# SparkFun_QwiicBus-Midpoint.net
KiCad netlist of a schematic drawn in EAGLE
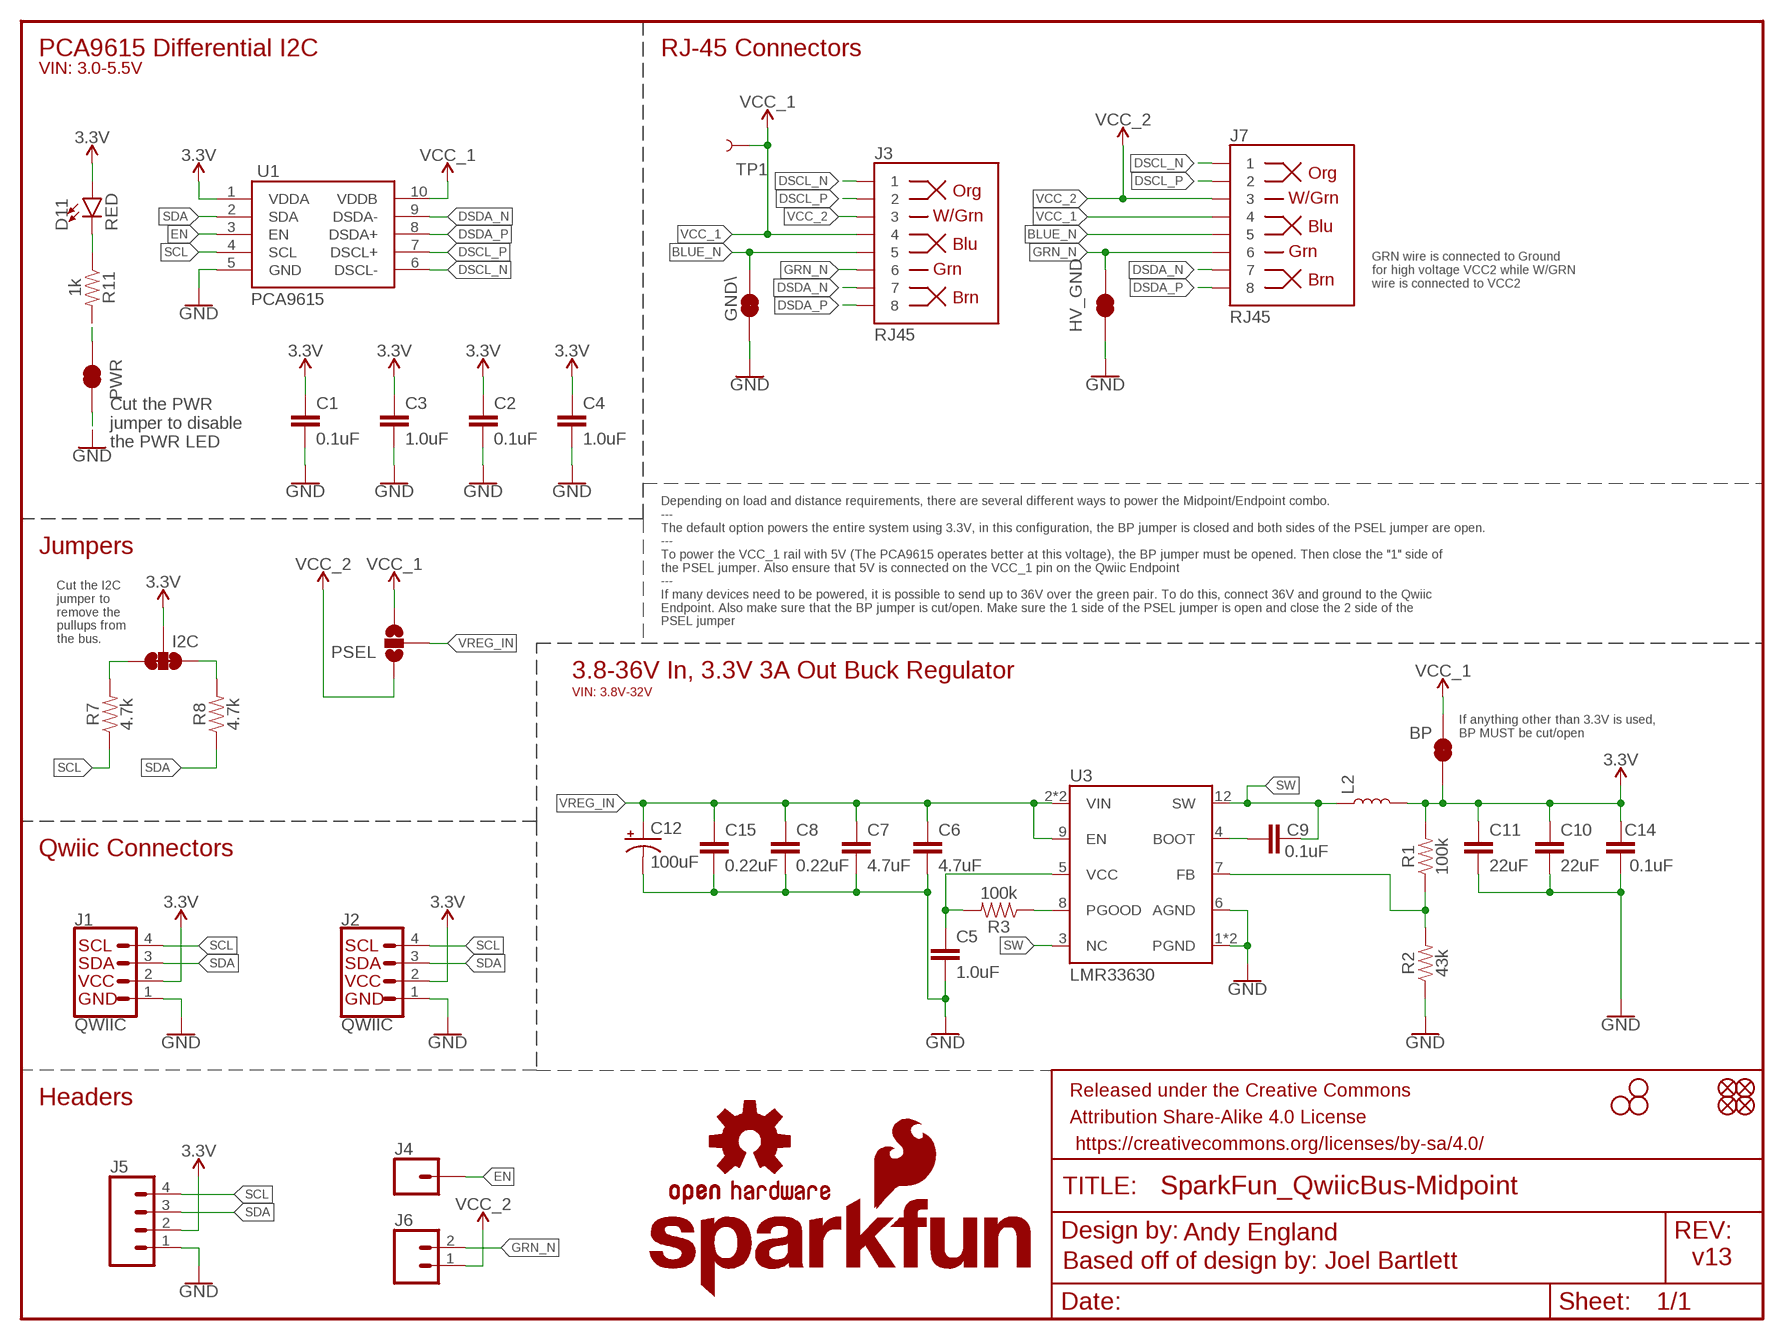
[diagram p0: schematic, sheet 1]

(export (version "E")
  (design (tool "Eeschema 10.0.6"))
  (components
    (comp (ref "BP")
      (value "JUMPER-SMT_2_NC_TRACE_SILK")
      (footprint "eagle-import:SMT-JUMPER_2_NC_TRACE_SILK")
      (libsource (lib "eagle-import") (part "JUMPER-SMT_2_NC_TRACE_SILK"))
    )
    (comp (ref "C1")
      (value "0.1uF")
      (footprint "eagle-import:0603")
      (libsource (lib "eagle-import") (part "0.1UF-0603-25V-(+80/-20%)"))
    )
    (comp (ref "C2")
      (value "0.1uF")
      (footprint "eagle-import:0603")
      (libsource (lib "eagle-import") (part "0.1UF-0603-25V-(+80/-20%)"))
    )
    (comp (ref "C3")
      (value "1.0uF")
      (footprint "eagle-import:0603")
      (libsource (lib "eagle-import") (part "1.0UF-0603-16V-10%"))
    )
    (comp (ref "C4")
      (value "1.0uF")
      (footprint "eagle-import:0603")
      (libsource (lib "eagle-import") (part "1.0UF-0603-16V-10%"))
    )
    (comp (ref "C5")
      (value "1.0uF")
      (footprint "eagle-import:0603")
      (libsource (lib "eagle-import") (part "1.0UF-0603-16V-10%"))
    )
    (comp (ref "C6")
      (value "4.7uF")
      (footprint "eagle-import:0805")
      (libsource (lib "eagle-import") (part "4.7UF-0805-50V-(10%)"))
    )
    (comp (ref "C7")
      (value "4.7uF")
      (footprint "eagle-import:0805")
      (libsource (lib "eagle-import") (part "4.7UF-0805-50V-(10%)"))
    )
    (comp (ref "C8")
      (value "0.22uF")
      (footprint "eagle-import:0603")
      (libsource (lib "eagle-import") (part "0.22UF-0603-50V-10%"))
    )
    (comp (ref "C9")
      (value "0.1uF")
      (footprint "eagle-import:0603")
      (libsource (lib "eagle-import") (part "0.1UF-0603-100V-10%"))
    )
    (comp (ref "C10")
      (value "22uF")
      (footprint "eagle-import:1210")
      (libsource (lib "eagle-import") (part "22UF-1210-16V-20%"))
    )
    (comp (ref "C11")
      (value "22uF")
      (footprint "eagle-import:1210")
      (libsource (lib "eagle-import") (part "22UF-1210-16V-20%"))
    )
    (comp (ref "C12")
      (value "100uF")
      (footprint "eagle-import:8X10.5")
      (libsource (lib "eagle-import") (part "100UF-POLAR-8X10.5-50V"))
    )
    (comp (ref "C14")
      (value "0.1uF")
      (footprint "eagle-import:0603")
      (libsource (lib "eagle-import") (part "0.1UF-0603-100V-10%"))
    )
    (comp (ref "C15")
      (value "0.22uF")
      (footprint "eagle-import:0603")
      (libsource (lib "eagle-import") (part "0.22UF-0603-50V-10%"))
    )
    (comp (ref "D11")
      (value "RED")
      (footprint "eagle-import:LED-0603")
      (libsource (lib "eagle-import") (part "LED-RED0603"))
    )
    (comp (ref "FD1")
      (value "FIDUCIALUFIDUCIAL")
      (footprint "eagle-import:FIDUCIAL-MICRO")
      (libsource (lib "eagle-import") (part "FIDUCIALUFIDUCIAL"))
    )
    (comp (ref "FD2")
      (value "FIDUCIALUFIDUCIAL")
      (footprint "eagle-import:FIDUCIAL-MICRO")
      (libsource (lib "eagle-import") (part "FIDUCIALUFIDUCIAL"))
    )
    (comp (ref "FD3")
      (value "FIDUCIALUFIDUCIAL")
      (footprint "eagle-import:FIDUCIAL-MICRO")
      (libsource (lib "eagle-import") (part "FIDUCIALUFIDUCIAL"))
    )
    (comp (ref "FD4")
      (value "FIDUCIALUFIDUCIAL")
      (footprint "eagle-import:FIDUCIAL-MICRO")
      (libsource (lib "eagle-import") (part "FIDUCIALUFIDUCIAL"))
    )
    (comp (ref "FRAME1")
      (value "FRAME-LETTER")
      (footprint "eagle-import:CREATIVE_COMMONS")
      (libsource (lib "eagle-import") (part "FRAME-LETTER"))
    )
    (comp (ref "GND\\")
      (value "JUMPER-SMT_2_NC_TRACE_SILK")
      (footprint "eagle-import:SMT-JUMPER_2_NC_TRACE_SILK")
      (libsource (lib "eagle-import") (part "JUMPER-SMT_2_NC_TRACE_SILK"))
    )
    (comp (ref "H2")
      (value "STAND-OFF")
      (footprint "eagle-import:STAND-OFF")
      (libsource (lib "eagle-import") (part "STAND-OFF"))
    )
    (comp (ref "H3")
      (value "STAND-OFF")
      (footprint "eagle-import:STAND-OFF")
      (libsource (lib "eagle-import") (part "STAND-OFF"))
    )
    (comp (ref "H4")
      (value "STAND-OFF")
      (footprint "eagle-import:STAND-OFF")
      (libsource (lib "eagle-import") (part "STAND-OFF"))
    )
    (comp (ref "HV_GND")
      (value "JUMPER-SMT_2_NC_TRACE_SILK")
      (footprint "eagle-import:SMT-JUMPER_2_NC_TRACE_SILK")
      (libsource (lib "eagle-import") (part "JUMPER-SMT_2_NC_TRACE_SILK"))
    )
    (comp (ref "I2C")
      (value "JUMPER-SMT_3_2-NC_TRACE_SILK")
      (footprint "eagle-import:SMT-JUMPER_3_2-NC_TRACE_SILK")
      (libsource (lib "eagle-import") (part "JUMPER-SMT_3_2-NC_TRACE_SILK"))
    )
    (comp (ref "J1")
      (value "QWIIC")
      (footprint "eagle-import:JST04_1MM_RA")
      (libsource (lib "eagle-import") (part "QWIIC_CONNECTORJS-1MM"))
    )
    (comp (ref "J2")
      (value "QWIIC")
      (footprint "eagle-import:JST04_1MM_RA")
      (libsource (lib "eagle-import") (part "QWIIC_CONNECTORJS-1MM"))
    )
    (comp (ref "J3")
      (value "RJ45")
      (footprint "eagle-import:RJ45-8")
      (libsource (lib "eagle-import") (part "RJ45-8"))
    )
    (comp (ref "J4")
      (value "CONN_01PTH_NO_SILK_YES_STOP")
      (footprint "eagle-import:1X01_NO_SILK")
      (libsource (lib "eagle-import") (part "CONN_01PTH_NO_SILK_YES_STOP"))
    )
    (comp (ref "J5")
      (value "CONN_041X04_NO_SILK")
      (footprint "eagle-import:1X04_NO_SILK")
      (libsource (lib "eagle-import") (part "CONN_041X04_NO_SILK"))
    )
    (comp (ref "J6")
      (value "CONN_021X02_NO_SILK")
      (footprint "eagle-import:1X02_NO_SILK")
      (libsource (lib "eagle-import") (part "CONN_021X02_NO_SILK"))
    )
    (comp (ref "J7")
      (value "RJ45")
      (footprint "eagle-import:RJ45-8")
      (libsource (lib "eagle-import") (part "RJ45-8"))
    )
    (comp (ref "L2")
      (value "2.2uH")
      (footprint "eagle-import:INDUCTOR_5X5MM")
      (libsource (lib "eagle-import") (part "2.2μH_SHIELDED_INDUCTOR_5X5"))
    )
    (comp (ref "LOGO1")
      (value "OSHW-LOGOM")
      (footprint "eagle-import:OSHW-LOGO-M")
      (libsource (lib "eagle-import") (part "OSHW-LOGOM"))
    )
    (comp (ref "LOGO3")
      (value "SFE_LOGO_FLAME.2_INCH")
      (footprint "eagle-import:SFE_LOGO_FLAME_.2")
      (libsource (lib "eagle-import") (part "SFE_LOGO_FLAME.2_INCH"))
    )
    (comp (ref "LOGO4")
      (value "SFE_LOGO_NAME_FLAME.1_INCH")
      (footprint "eagle-import:SFE_LOGO_NAME_FLAME_.1")
      (libsource (lib "eagle-import") (part "SFE_LOGO_NAME_FLAME.1_INCH"))
    )
    (comp (ref "PSEL")
      (value "JUMPER-SMT_3_NO_SILK")
      (footprint "eagle-import:SMT-JUMPER_3_NO_SILK")
      (libsource (lib "eagle-import") (part "JUMPER-SMT_3_NO_SILK"))
    )
    (comp (ref "PWR")
      (value "JUMPER-SMT_2_NC_TRACE_SILK")
      (footprint "eagle-import:SMT-JUMPER_2_NC_TRACE_SILK")
      (libsource (lib "eagle-import") (part "JUMPER-SMT_2_NC_TRACE_SILK"))
    )
    (comp (ref "R1")
      (value "100k")
      (footprint "eagle-import:0603")
      (libsource (lib "eagle-import") (part "100KOHM-0603-1/10W-1%"))
    )
    (comp (ref "R2")
      (value "43k")
      (footprint "eagle-import:0603")
      (libsource (lib "eagle-import") (part "43KOHM-0603-1/10W-1%"))
    )
    (comp (ref "R3")
      (value "100k")
      (footprint "eagle-import:0603")
      (libsource (lib "eagle-import") (part "100KOHM-0603-1/10W-1%"))
    )
    (comp (ref "R7")
      (value "4.7k")
      (footprint "eagle-import:0603")
      (libsource (lib "eagle-import") (part "4.7KOHM-0603-1/10W-1%"))
    )
    (comp (ref "R8")
      (value "4.7k")
      (footprint "eagle-import:0603")
      (libsource (lib "eagle-import") (part "4.7KOHM-0603-1/10W-1%"))
    )
    (comp (ref "R11")
      (value "1k")
      (footprint "eagle-import:0603")
      (libsource (lib "eagle-import") (part "1KOHM-0603-1/10W-1%"))
    )
    (comp (ref "TP1")
      (value "TEST-POINT3")
      (footprint "eagle-import:PAD.03X.03")
      (libsource (lib "eagle-import") (part "TEST-POINT3"))
    )
    (comp (ref "U1")
      (value "PCA9615")
      (footprint "eagle-import:TSSOP10")
      (libsource (lib "eagle-import") (part "PCA9615"))
    )
    (comp (ref "U3")
      (value "LMR33630")
      (footprint "eagle-import:VQFN-HR-12")
      (libsource (lib "eagle-import") (part "LMR33630"))
    )
  )
  (nets
    (net (code "1") (name "3.3V") (class "Default")
      (node (ref "BP") (pin "1") (pinfunction "1_1") (pintype "passive"))
      (node (ref "C1") (pin "1") (pinfunction "1_1") (pintype "passive"))
      (node (ref "C10") (pin "1") (pinfunction "1_1") (pintype "passive"))
      (node (ref "C11") (pin "1") (pinfunction "1_1") (pintype "passive"))
      (node (ref "C14") (pin "1") (pinfunction "1_1") (pintype "passive"))
      (node (ref "C2") (pin "1") (pinfunction "1_1") (pintype "passive"))
      (node (ref "C3") (pin "1") (pinfunction "1_1") (pintype "passive"))
      (node (ref "C4") (pin "1") (pinfunction "1_1") (pintype "passive"))
      (node (ref "D11") (pin "A") (pinfunction "A_A") (pintype "passive"))
      (node (ref "I2C") (pin "2") (pinfunction "2_2") (pintype "passive"))
      (node (ref "J1") (pin "2") (pinfunction "2_2") (pintype "power_in"))
      (node (ref "J2") (pin "2") (pinfunction "2_2") (pintype "power_in"))
      (node (ref "J5") (pin "2") (pinfunction "2_2") (pintype "passive"))
      (node (ref "L2") (pin "P$2") (pinfunction "2_P$2") (pintype "passive"))
      (node (ref "R1") (pin "2") (pinfunction "2_2") (pintype "passive"))
      (node (ref "U1") (pin "1") (pinfunction "VDDA_1") (pintype "bidirectional"))
    )
    (net (code "2") (name "BLUE_N") (class "Default")
      (node (ref "GND\\") (pin "2") (pinfunction "2_2") (pintype "passive"))
      (node (ref "J3") (pin "5") (pinfunction "5_5") (pintype "bidirectional"))
      (node (ref "J7") (pin "5") (pinfunction "5_5") (pintype "bidirectional"))
    )
    (net (code "3") (name "DSCL_N") (class "Default")
      (node (ref "J3") (pin "1") (pinfunction "1_1") (pintype "bidirectional"))
      (node (ref "J7") (pin "1") (pinfunction "1_1") (pintype "bidirectional"))
      (node (ref "U1") (pin "6") (pinfunction "DSCL-_6") (pintype "bidirectional"))
    )
    (net (code "4") (name "DSCL_P") (class "Default")
      (node (ref "J3") (pin "2") (pinfunction "2_2") (pintype "bidirectional"))
      (node (ref "J7") (pin "2") (pinfunction "2_2") (pintype "bidirectional"))
      (node (ref "U1") (pin "7") (pinfunction "DSCL+_7") (pintype "bidirectional"))
    )
    (net (code "5") (name "DSDA_N") (class "Default")
      (node (ref "J3") (pin "7") (pinfunction "7_7") (pintype "bidirectional"))
      (node (ref "J7") (pin "7") (pinfunction "7_7") (pintype "bidirectional"))
      (node (ref "U1") (pin "9") (pinfunction "DSDA-_9") (pintype "bidirectional"))
    )
    (net (code "6") (name "DSDA_P") (class "Default")
      (node (ref "J3") (pin "8") (pinfunction "8_8") (pintype "bidirectional"))
      (node (ref "J7") (pin "8") (pinfunction "8_8") (pintype "bidirectional"))
      (node (ref "U1") (pin "8") (pinfunction "DSDA+_8") (pintype "bidirectional"))
    )
    (net (code "7") (name "EN") (class "Default")
      (node (ref "J4") (pin "1") (pinfunction "1_1") (pintype "passive"))
      (node (ref "U1") (pin "3") (pinfunction "EN_3") (pintype "bidirectional"))
    )
    (net (code "8") (name "GND") (class "Default")
      (node (ref "C1") (pin "2") (pinfunction "2_2") (pintype "passive"))
      (node (ref "C10") (pin "2") (pinfunction "2_2") (pintype "passive"))
      (node (ref "C11") (pin "2") (pinfunction "2_2") (pintype "passive"))
      (node (ref "C12") (pin "-") (pinfunction "-_-") (pintype "passive"))
      (node (ref "C14") (pin "2") (pinfunction "2_2") (pintype "passive"))
      (node (ref "C15") (pin "2") (pinfunction "2_2") (pintype "passive"))
      (node (ref "C2") (pin "2") (pinfunction "2_2") (pintype "passive"))
      (node (ref "C3") (pin "2") (pinfunction "2_2") (pintype "passive"))
      (node (ref "C4") (pin "2") (pinfunction "2_2") (pintype "passive"))
      (node (ref "C5") (pin "2") (pinfunction "2_2") (pintype "passive"))
      (node (ref "C6") (pin "2") (pinfunction "2_2") (pintype "passive"))
      (node (ref "C7") (pin "2") (pinfunction "2_2") (pintype "passive"))
      (node (ref "C8") (pin "2") (pinfunction "2_2") (pintype "passive"))
      (node (ref "GND\\") (pin "1") (pinfunction "1_1") (pintype "passive"))
      (node (ref "HV_GND") (pin "1") (pinfunction "1_1") (pintype "passive"))
      (node (ref "J1") (pin "1") (pinfunction "1_1") (pintype "power_in"))
      (node (ref "J2") (pin "1") (pinfunction "1_1") (pintype "power_in"))
      (node (ref "J5") (pin "1") (pinfunction "1_1") (pintype "passive"))
      (node (ref "PWR") (pin "1") (pinfunction "1_1") (pintype "passive"))
      (node (ref "R2") (pin "1") (pinfunction "1_1") (pintype "passive"))
      (node (ref "U1") (pin "5") (pinfunction "GND_5") (pintype "bidirectional"))
      (node (ref "U3") (pin "1") (pinfunction "PGND_1") (pintype "bidirectional"))
      (node (ref "U3") (pin "11") (pinfunction "PGND_11") (pintype "bidirectional"))
      (node (ref "U3") (pin "6") (pinfunction "AGND_6") (pintype "bidirectional"))
    )
    (net (code "9") (name "GRN_N") (class "Default")
      (node (ref "HV_GND") (pin "2") (pinfunction "2_2") (pintype "passive"))
      (node (ref "J3") (pin "6") (pinfunction "6_6") (pintype "bidirectional"))
      (node (ref "J6") (pin "2") (pinfunction "2_2") (pintype "passive"))
      (node (ref "J7") (pin "6") (pinfunction "6_6") (pintype "bidirectional"))
    )
    (net (code "10") (name "Net-(D11-PadC)") (class "Default")
      (node (ref "D11") (pin "C") (pinfunction "C_C") (pintype "passive"))
      (node (ref "R11") (pin "1") (pinfunction "1_1") (pintype "passive"))
    )
    (net (code "11") (name "Net-(I2C-Pad1)") (class "Default")
      (node (ref "I2C") (pin "1") (pinfunction "1_1") (pintype "passive"))
      (node (ref "R8") (pin "2") (pinfunction "2_2") (pintype "passive"))
    )
    (net (code "12") (name "Net-(I2C-Pad3)") (class "Default")
      (node (ref "I2C") (pin "3") (pinfunction "3_3") (pintype "passive"))
      (node (ref "R7") (pin "2") (pinfunction "2_2") (pintype "passive"))
    )
    (net (code "13") (name "Net-(PWR-Pad2)") (class "Default")
      (node (ref "PWR") (pin "2") (pinfunction "2_2") (pintype "passive"))
      (node (ref "R11") (pin "2") (pinfunction "2_2") (pintype "passive"))
    )
    (net (code "14") (name "Net-(U3-BOOT)") (class "Default")
      (node (ref "C9") (pin "1") (pinfunction "1_1") (pintype "passive"))
      (node (ref "U3") (pin "4") (pinfunction "BOOT_4") (pintype "bidirectional"))
    )
    (net (code "15") (name "Net-(U3-FB)") (class "Default")
      (node (ref "R1") (pin "1") (pinfunction "1_1") (pintype "passive"))
      (node (ref "R2") (pin "2") (pinfunction "2_2") (pintype "passive"))
      (node (ref "U3") (pin "7") (pinfunction "FB_7") (pintype "bidirectional"))
    )
    (net (code "16") (name "Net-(U3-PGOOD)") (class "Default")
      (node (ref "R3") (pin "1") (pinfunction "1_1") (pintype "passive"))
      (node (ref "U3") (pin "8") (pinfunction "PGOOD_8") (pintype "bidirectional"))
    )
    (net (code "17") (name "Net-(U3-VCC)") (class "Default")
      (node (ref "C5") (pin "1") (pinfunction "1_1") (pintype "passive"))
      (node (ref "R3") (pin "2") (pinfunction "2_2") (pintype "passive"))
      (node (ref "U3") (pin "5") (pinfunction "VCC_5") (pintype "bidirectional"))
    )
    (net (code "18") (name "SCL") (class "Default")
      (node (ref "J1") (pin "4") (pinfunction "4_4") (pintype "passive"))
      (node (ref "J2") (pin "4") (pinfunction "4_4") (pintype "passive"))
      (node (ref "J5") (pin "4") (pinfunction "4_4") (pintype "passive"))
      (node (ref "R7") (pin "1") (pinfunction "1_1") (pintype "passive"))
      (node (ref "U1") (pin "4") (pinfunction "SCL_4") (pintype "bidirectional"))
    )
    (net (code "19") (name "SDA") (class "Default")
      (node (ref "J1") (pin "3") (pinfunction "3_3") (pintype "passive"))
      (node (ref "J2") (pin "3") (pinfunction "3_3") (pintype "passive"))
      (node (ref "J5") (pin "3") (pinfunction "3_3") (pintype "passive"))
      (node (ref "R8") (pin "1") (pinfunction "1_1") (pintype "passive"))
      (node (ref "U1") (pin "2") (pinfunction "SDA_2") (pintype "bidirectional"))
    )
    (net (code "20") (name "SW") (class "Default")
      (node (ref "C9") (pin "2") (pinfunction "2_2") (pintype "passive"))
      (node (ref "L2") (pin "P$1") (pinfunction "1_P$1") (pintype "passive"))
      (node (ref "U3") (pin "12") (pinfunction "SW_12") (pintype "bidirectional"))
      (node (ref "U3") (pin "3") (pinfunction "NC_3") (pintype "bidirectional"))
    )
    (net (code "21") (name "VCC_1") (class "Default")
      (node (ref "BP") (pin "2") (pinfunction "2_2") (pintype "passive"))
      (node (ref "J3") (pin "4") (pinfunction "4_4") (pintype "bidirectional"))
      (node (ref "J7") (pin "4") (pinfunction "4_4") (pintype "bidirectional"))
      (node (ref "PSEL") (pin "3") (pinfunction "3_3") (pintype "passive"))
      (node (ref "TP1") (pin "P$1") (pinfunction "1_P$1") (pintype "bidirectional"))
      (node (ref "U1") (pin "10") (pinfunction "VDDB_10") (pintype "bidirectional"))
    )
    (net (code "22") (name "VCC_2") (class "Default")
      (node (ref "J3") (pin "3") (pinfunction "3_3") (pintype "bidirectional"))
      (node (ref "J6") (pin "1") (pinfunction "1_1") (pintype "passive"))
      (node (ref "J7") (pin "3") (pinfunction "3_3") (pintype "bidirectional"))
      (node (ref "PSEL") (pin "1") (pinfunction "1_1") (pintype "passive"))
    )
    (net (code "23") (name "VREG_IN") (class "Default")
      (node (ref "C12") (pin "+") (pinfunction "+_+") (pintype "passive"))
      (node (ref "C15") (pin "1") (pinfunction "1_1") (pintype "passive"))
      (node (ref "C6") (pin "1") (pinfunction "1_1") (pintype "passive"))
      (node (ref "C7") (pin "1") (pinfunction "1_1") (pintype "passive"))
      (node (ref "C8") (pin "1") (pinfunction "1_1") (pintype "passive"))
      (node (ref "PSEL") (pin "2") (pinfunction "2_2") (pintype "passive"))
      (node (ref "U3") (pin "10") (pinfunction "VIN_10") (pintype "bidirectional"))
      (node (ref "U3") (pin "2") (pinfunction "VIN_2") (pintype "bidirectional"))
      (node (ref "U3") (pin "9") (pinfunction "EN_9") (pintype "bidirectional"))
    )
  )
)
